# untitled.net
KiCad netlist of a schematic drawn in EAGLE
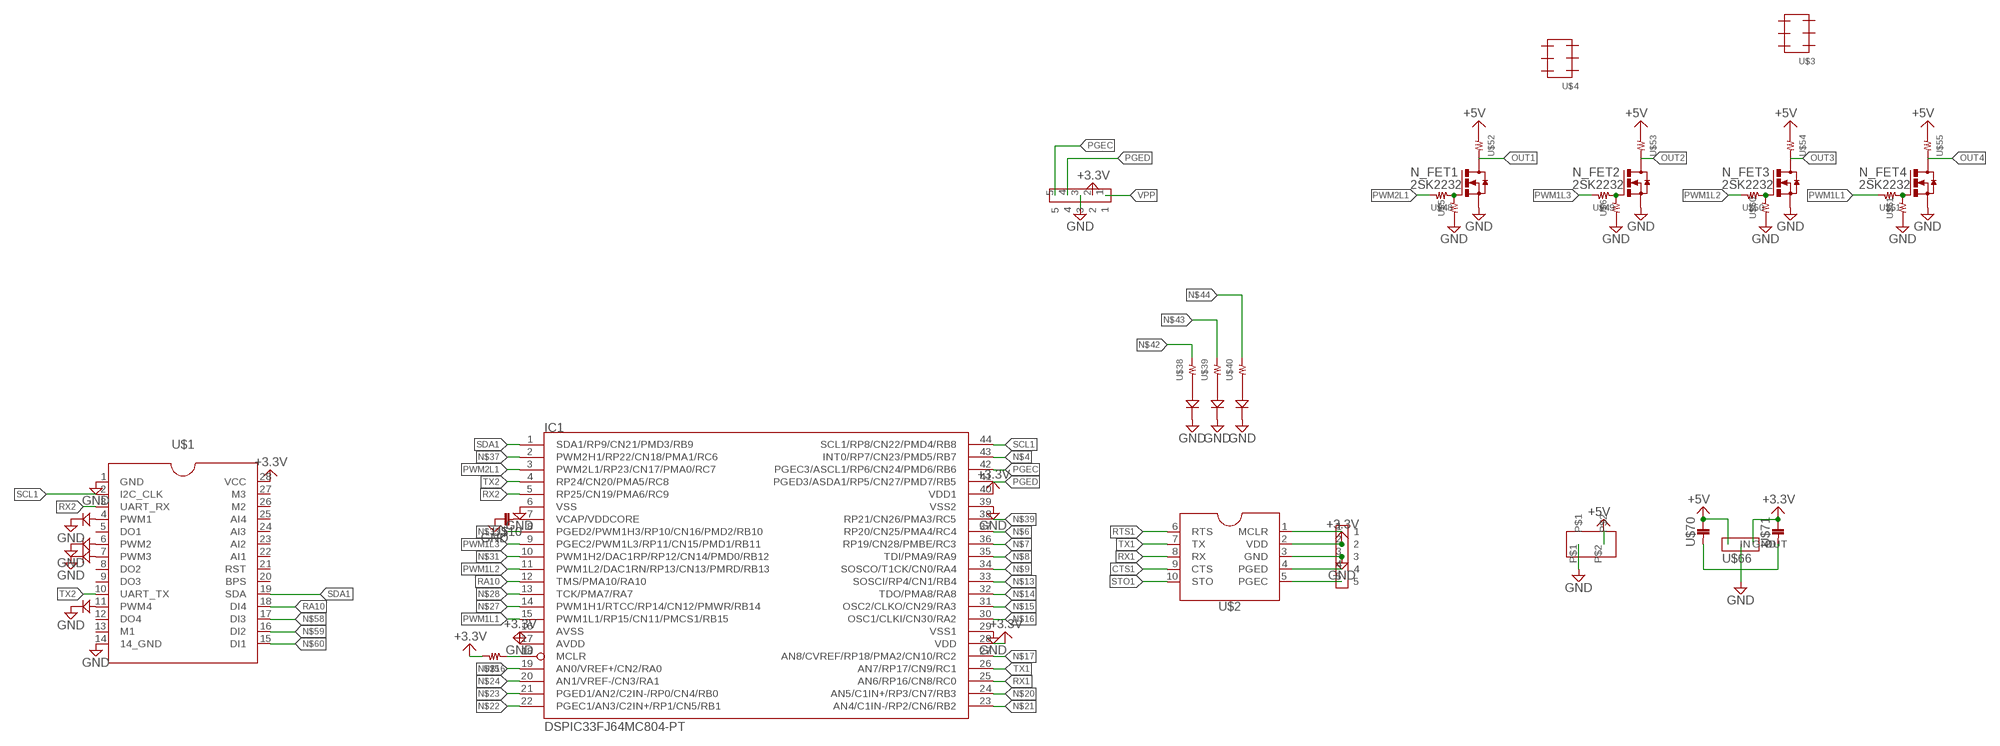
[diagram p0: schematic, sheet 1]

(export (version "E")
  (design (tool "Eeschema 10.0.6"))
  (components
    (comp (ref "IC1")
      (value "DSPIC33FJ64MC804-PT")
      (footprint "eagle-import:TQFP44")
      (libsource (lib "eagle-import") (part "DSPIC33FJ64MC804-PT"))
    )
    (comp (ref "N_FET1")
      (value "2SK2232")
      (footprint "eagle-import:TO-220_V")
      (libsource (lib "eagle-import") (part "2SK2232"))
    )
    (comp (ref "N_FET2")
      (value "2SK2232")
      (footprint "eagle-import:TO-220_V")
      (libsource (lib "eagle-import") (part "2SK2232"))
    )
    (comp (ref "N_FET3")
      (value "2SK2232")
      (footprint "eagle-import:TO-220_V")
      (libsource (lib "eagle-import") (part "2SK2232"))
    )
    (comp (ref "N_FET4")
      (value "2SK2232")
      (footprint "eagle-import:TO-220_V")
      (libsource (lib "eagle-import") (part "2SK2232"))
    )
    (comp (ref "U$1")
      (value "TWE-LITE")
      (footprint "eagle-import:DIP28")
      (libsource (lib "eagle-import") (part "TWE-LITE"))
    )
    (comp (ref "U$2")
      (value "SBDBT")
      (footprint "eagle-import:DIL10")
      (libsource (lib "eagle-import") (part "SBDBT"))
    )
    (comp (ref "U$3")
      (value "PIN_HEADER_32")
      (footprint "eagle-import:PIN_HEADER_3_2")
      (libsource (lib "eagle-import") (part "PIN_HEADER_32"))
    )
    (comp (ref "U$4")
      (value "PIN_HEADER_32")
      (footprint "eagle-import:PIN_HEADER_3_2")
      (libsource (lib "eagle-import") (part "PIN_HEADER_32"))
    )
    (comp (ref "U$5")
      (value "RESISTOR__SMD")
      (footprint "eagle-import:1608")
      (libsource (lib "eagle-import") (part "RESISTOR__SMD"))
    )
    (comp (ref "U$6")
      (value "RESISTOR__SMD")
      (footprint "eagle-import:1608")
      (libsource (lib "eagle-import") (part "RESISTOR__SMD"))
    )
    (comp (ref "U$10")
      (value "2012")
      (footprint "eagle-import:2012")
      (libsource (lib "eagle-import") (part "2012"))
    )
    (comp (ref "U$16")
      (value "RESISTOR__SMD")
      (footprint "eagle-import:1608")
      (libsource (lib "eagle-import") (part "RESISTOR__SMD"))
    )
    (comp (ref "U$18")
      (value "PIN_HEADER_5")
      (footprint "eagle-import:PIN_HEADER_5")
      (libsource (lib "eagle-import") (part "PIN_HEADER_5"))
    )
    (comp (ref "U$24")
      (value "PIN_HEADER_5")
      (footprint "eagle-import:PIN_HEADER_5")
      (libsource (lib "eagle-import") (part "PIN_HEADER_5"))
    )
    (comp (ref "U$27")
      (value "5MMLED")
      (footprint "eagle-import:5MM")
      (libsource (lib "eagle-import") (part "5MMLED"))
    )
    (comp (ref "U$28")
      (value "5MMLED")
      (footprint "eagle-import:5MM")
      (libsource (lib "eagle-import") (part "5MMLED"))
    )
    (comp (ref "U$29")
      (value "5MMLED")
      (footprint "eagle-import:5MM")
      (libsource (lib "eagle-import") (part "5MMLED"))
    )
    (comp (ref "U$30")
      (value "5MMLED")
      (footprint "eagle-import:5MM")
      (libsource (lib "eagle-import") (part "5MMLED"))
    )
    (comp (ref "U$35")
      (value "3MMLED")
      (footprint "eagle-import:3MM")
      (libsource (lib "eagle-import") (part "3MMLED"))
    )
    (comp (ref "U$36")
      (value "3MMLED")
      (footprint "eagle-import:3MM")
      (libsource (lib "eagle-import") (part "3MMLED"))
    )
    (comp (ref "U$37")
      (value "3MMLED")
      (footprint "eagle-import:3MM")
      (libsource (lib "eagle-import") (part "3MMLED"))
    )
    (comp (ref "U$38")
      (value "RESISTOR__SMD")
      (footprint "eagle-import:1608")
      (libsource (lib "eagle-import") (part "RESISTOR__SMD"))
    )
    (comp (ref "U$39")
      (value "RESISTOR__SMD")
      (footprint "eagle-import:1608")
      (libsource (lib "eagle-import") (part "RESISTOR__SMD"))
    )
    (comp (ref "U$40")
      (value "RESISTOR__SMD")
      (footprint "eagle-import:1608")
      (libsource (lib "eagle-import") (part "RESISTOR__SMD"))
    )
    (comp (ref "U$48")
      (value "RESISTOR__SMD")
      (footprint "eagle-import:1608")
      (libsource (lib "eagle-import") (part "RESISTOR__SMD"))
    )
    (comp (ref "U$49")
      (value "RESISTOR__SMD")
      (footprint "eagle-import:1608")
      (libsource (lib "eagle-import") (part "RESISTOR__SMD"))
    )
    (comp (ref "U$50")
      (value "RESISTOR__SMD")
      (footprint "eagle-import:1608")
      (libsource (lib "eagle-import") (part "RESISTOR__SMD"))
    )
    (comp (ref "U$51")
      (value "RESISTOR__SMD")
      (footprint "eagle-import:1608")
      (libsource (lib "eagle-import") (part "RESISTOR__SMD"))
    )
    (comp (ref "U$52")
      (value "RESISTOR__SMD")
      (footprint "eagle-import:1608")
      (libsource (lib "eagle-import") (part "RESISTOR__SMD"))
    )
    (comp (ref "U$53")
      (value "RESISTOR__SMD")
      (footprint "eagle-import:1608")
      (libsource (lib "eagle-import") (part "RESISTOR__SMD"))
    )
    (comp (ref "U$54")
      (value "RESISTOR__SMD")
      (footprint "eagle-import:1608")
      (libsource (lib "eagle-import") (part "RESISTOR__SMD"))
    )
    (comp (ref "U$55")
      (value "RESISTOR__SMD")
      (footprint "eagle-import:1608")
      (libsource (lib "eagle-import") (part "RESISTOR__SMD"))
    )
    (comp (ref "U$60")
      (value "RESISTOR__SMD")
      (footprint "eagle-import:1608")
      (libsource (lib "eagle-import") (part "RESISTOR__SMD"))
    )
    (comp (ref "U$61")
      (value "RESISTOR__SMD")
      (footprint "eagle-import:1608")
      (libsource (lib "eagle-import") (part "RESISTOR__SMD"))
    )
    (comp (ref "U$66")
      (value "TA48M033F")
      (footprint "eagle-import:ＴＡ４８")
      (libsource (lib "eagle-import") (part "TA48M033F"))
    )
    (comp (ref "U$70")
      (value "1608")
      (footprint "eagle-import:1608")
      (libsource (lib "eagle-import") (part "1608"))
    )
    (comp (ref "U$71")
      (value "3225")
      (footprint "eagle-import:3225")
      (libsource (lib "eagle-import") (part "3225"))
    )
    (comp (ref "U$72")
      (value "PIN_HEADER_2")
      (footprint "eagle-import:PIN_HEADER_2S")
      (libsource (lib "eagle-import") (part "PIN_HEADER_2"))
    )
  )
  (nets
    (net (code "1") (name "+3.3V") (class "Default")
      (node (ref "IC1") (pin "17") (pinfunction "AVDD_17") (pintype "power_in"))
      (node (ref "IC1") (pin "28") (pinfunction "VDD_28") (pintype "power_in"))
      (node (ref "IC1") (pin "40") (pinfunction "VDD1_40") (pintype "power_in"))
      (node (ref "U$1") (pin "28") (pinfunction "VCC_28") (pintype "passive"))
      (node (ref "U$16") (pin "2") (pinfunction "P$2_2") (pintype "passive"))
      (node (ref "U$18") (pin "2") (pinfunction "2_2") (pintype "bidirectional"))
      (node (ref "U$2") (pin "2") (pinfunction "VDD_2") (pintype "passive"))
      (node (ref "U$24") (pin "2") (pinfunction "2_2") (pintype "bidirectional"))
      (node (ref "U$66") (pin "3") (pinfunction "OUT_3") (pintype "bidirectional"))
      (node (ref "U$71") (pin "P$1") (pinfunction "1_P$1") (pintype "passive"))
    )
    (net (code "2") (name "+5V") (class "Default")
      (node (ref "U$52") (pin "1") (pinfunction "P$1_1") (pintype "passive"))
      (node (ref "U$53") (pin "1") (pinfunction "P$1_1") (pintype "passive"))
      (node (ref "U$54") (pin "1") (pinfunction "P$1_1") (pintype "passive"))
      (node (ref "U$55") (pin "1") (pinfunction "P$1_1") (pintype "passive"))
      (node (ref "U$66") (pin "1") (pinfunction "IN_1") (pintype "bidirectional"))
      (node (ref "U$70") (pin "P$1") (pinfunction "1_P$1") (pintype "passive"))
      (node (ref "U$72") (pin "P$2") (pinfunction "P$2_P$2") (pintype "bidirectional"))
    )
    (net (code "3") (name "CTS1") (class "Default")
      (node (ref "U$2") (pin "9") (pinfunction "CTS_9") (pintype "passive"))
    )
    (net (code "4") (name "GND") (class "Default")
      (node (ref "IC1") (pin "16") (pinfunction "AVSS_16") (pintype "power_in"))
      (node (ref "IC1") (pin "29") (pinfunction "VSS1_29") (pintype "power_in"))
      (node (ref "IC1") (pin "39") (pinfunction "VSS2_39") (pintype "power_in"))
      (node (ref "IC1") (pin "6") (pinfunction "VSS_6") (pintype "power_in"))
      (node (ref "N_FET1") (pin "3") (pinfunction "S_3") (pintype "passive"))
      (node (ref "N_FET2") (pin "3") (pinfunction "S_3") (pintype "passive"))
      (node (ref "N_FET3") (pin "3") (pinfunction "S_3") (pintype "passive"))
      (node (ref "N_FET4") (pin "3") (pinfunction "S_3") (pintype "passive"))
      (node (ref "U$1") (pin "1") (pinfunction "GND_1") (pintype "passive"))
      (node (ref "U$1") (pin "14") (pinfunction "14_GND_14") (pintype "passive"))
      (node (ref "U$10") (pin "1") (pinfunction "1_1") (pintype "passive"))
      (node (ref "U$18") (pin "3") (pinfunction "3_3") (pintype "bidirectional"))
      (node (ref "U$2") (pin "3") (pinfunction "GND_3") (pintype "passive"))
      (node (ref "U$24") (pin "3") (pinfunction "3_3") (pintype "bidirectional"))
      (node (ref "U$27") (pin "K") (pinfunction "K_K") (pintype "bidirectional"))
      (node (ref "U$28") (pin "K") (pinfunction "K_K") (pintype "bidirectional"))
      (node (ref "U$29") (pin "K") (pinfunction "K_K") (pintype "bidirectional"))
      (node (ref "U$30") (pin "K") (pinfunction "K_K") (pintype "bidirectional"))
      (node (ref "U$35") (pin "K") (pinfunction "K_K") (pintype "bidirectional"))
      (node (ref "U$36") (pin "K") (pinfunction "K_K") (pintype "bidirectional"))
      (node (ref "U$37") (pin "K") (pinfunction "K_K") (pintype "bidirectional"))
      (node (ref "U$5") (pin "1") (pinfunction "P$1_1") (pintype "passive"))
      (node (ref "U$6") (pin "1") (pinfunction "P$1_1") (pintype "passive"))
      (node (ref "U$60") (pin "1") (pinfunction "P$1_1") (pintype "passive"))
      (node (ref "U$61") (pin "1") (pinfunction "P$1_1") (pintype "passive"))
      (node (ref "U$66") (pin "2") (pinfunction "GND_2") (pintype "bidirectional"))
      (node (ref "U$70") (pin "P$2") (pinfunction "2_P$2") (pintype "passive"))
      (node (ref "U$71") (pin "P$2") (pinfunction "2_P$2") (pintype "passive"))
      (node (ref "U$72") (pin "P$1") (pinfunction "P$1_P$1") (pintype "bidirectional"))
    )
    (net (code "5") (name "N$4") (class "Default")
      (node (ref "IC1") (pin "43") (pinfunction "INT0/RP7/CN23/PMD5/RB7_43") (pintype "bidirectional"))
    )
    (net (code "6") (name "N$6") (class "Default")
      (node (ref "IC1") (pin "37") (pinfunction "RP20/CN25/PMA4/RC4_37") (pintype "bidirectional"))
    )
    (net (code "7") (name "N$7") (class "Default")
      (node (ref "IC1") (pin "36") (pinfunction "RP19/CN28/PMBE/RC3_36") (pintype "bidirectional"))
    )
    (net (code "8") (name "N$8") (class "Default")
      (node (ref "IC1") (pin "35") (pinfunction "TDI/PMA9/RA9_35") (pintype "bidirectional"))
    )
    (net (code "9") (name "N$9") (class "Default")
      (node (ref "IC1") (pin "34") (pinfunction "SOSCO/T1CK/CN0/RA4_34") (pintype "bidirectional"))
    )
    (net (code "10") (name "N$13") (class "Default")
      (node (ref "IC1") (pin "33") (pinfunction "SOSCI/RP4/CN1/RB4_33") (pintype "bidirectional"))
    )
    (net (code "11") (name "N$14") (class "Default")
      (node (ref "IC1") (pin "32") (pinfunction "TDO/PMA8/RA8_32") (pintype "bidirectional"))
    )
    (net (code "12") (name "N$15") (class "Default")
      (node (ref "IC1") (pin "31") (pinfunction "OSC2/CLKO/CN29/RA3_31") (pintype "bidirectional"))
    )
    (net (code "13") (name "N$16") (class "Default")
      (node (ref "IC1") (pin "30") (pinfunction "OSC1/CLKI/CN30/RA2_30") (pintype "bidirectional"))
    )
    (net (code "14") (name "N$17") (class "Default")
      (node (ref "IC1") (pin "27") (pinfunction "AN8/CVREF/RP18/PMA2/CN10/RC2_27") (pintype "bidirectional"))
    )
    (net (code "15") (name "N$20") (class "Default")
      (node (ref "IC1") (pin "24") (pinfunction "AN5/C1IN+/RP3/CN7/RB3_24") (pintype "bidirectional"))
    )
    (net (code "16") (name "N$21") (class "Default")
      (node (ref "IC1") (pin "23") (pinfunction "AN4/C1IN-/RP2/CN6/RB2_23") (pintype "bidirectional"))
    )
    (net (code "17") (name "N$22") (class "Default")
      (node (ref "IC1") (pin "22") (pinfunction "PGEC1/AN3/C2IN+/RP1/CN5/RB1_22") (pintype "bidirectional"))
    )
    (net (code "18") (name "N$23") (class "Default")
      (node (ref "IC1") (pin "21") (pinfunction "PGED1/AN2/C2IN-/RP0/CN4/RB0_21") (pintype "bidirectional"))
    )
    (net (code "19") (name "N$24") (class "Default")
      (node (ref "IC1") (pin "20") (pinfunction "AN1/VREF-/CN3/RA1_20") (pintype "bidirectional"))
    )
    (net (code "20") (name "N$25") (class "Default")
      (node (ref "IC1") (pin "19") (pinfunction "AN0/VREF+/CN2/RA0_19") (pintype "bidirectional"))
    )
    (net (code "21") (name "N$27") (class "Default")
      (node (ref "IC1") (pin "14") (pinfunction "PWM1H1/RTCC/RP14/CN12/PMWR/RB14_14") (pintype "bidirectional"))
    )
    (net (code "22") (name "N$28") (class "Default")
      (node (ref "IC1") (pin "13") (pinfunction "TCK/PMA7/RA7_13") (pintype "bidirectional"))
    )
    (net (code "23") (name "N$31") (class "Default")
      (node (ref "IC1") (pin "10") (pinfunction "PWM1H2/DAC1RP/RP12/CN14/PMD0/RB12_10") (pintype "bidirectional"))
    )
    (net (code "24") (name "N$33") (class "Default")
      (node (ref "IC1") (pin "8") (pinfunction "PGED2/PWM1H3/RP10/CN16/PMD2/RB10_8") (pintype "bidirectional"))
    )
    (net (code "25") (name "N$37") (class "Default")
      (node (ref "IC1") (pin "2") (pinfunction "PWM2H1/RP22/CN18/PMA1/RC6_2") (pintype "bidirectional"))
    )
    (net (code "26") (name "N$39") (class "Default")
      (node (ref "IC1") (pin "38") (pinfunction "RP21/CN26/PMA3/RC5_38") (pintype "bidirectional"))
    )
    (net (code "27") (name "N$42") (class "Default")
      (node (ref "U$38") (pin "2") (pinfunction "P$2_2") (pintype "passive"))
    )
    (net (code "28") (name "N$43") (class "Default")
      (node (ref "U$39") (pin "2") (pinfunction "P$2_2") (pintype "passive"))
    )
    (net (code "29") (name "N$44") (class "Default")
      (node (ref "U$40") (pin "2") (pinfunction "P$2_2") (pintype "passive"))
    )
    (net (code "30") (name "N$58") (class "Default")
      (node (ref "U$1") (pin "17") (pinfunction "DI3_17") (pintype "passive"))
    )
    (net (code "31") (name "N$59") (class "Default")
      (node (ref "U$1") (pin "16") (pinfunction "DI2_16") (pintype "passive"))
    )
    (net (code "32") (name "N$60") (class "Default")
      (node (ref "U$1") (pin "15") (pinfunction "DI1_15") (pintype "passive"))
    )
    (net (code "33") (name "Net-(IC1-VCAP{slash}VDDCORE)") (class "Default")
      (node (ref "IC1") (pin "7") (pinfunction "VCAP/VDDCORE_7") (pintype "power_in"))
      (node (ref "U$10") (pin "2") (pinfunction "2_2") (pintype "passive"))
    )
    (net (code "34") (name "Net-(N_FET1-G)") (class "Default")
      (node (ref "N_FET1") (pin "1") (pinfunction "G_1") (pintype "passive"))
      (node (ref "U$48") (pin "1") (pinfunction "P$1_1") (pintype "passive"))
      (node (ref "U$5") (pin "2") (pinfunction "P$2_2") (pintype "passive"))
    )
    (net (code "35") (name "Net-(N_FET2-G)") (class "Default")
      (node (ref "N_FET2") (pin "1") (pinfunction "G_1") (pintype "passive"))
      (node (ref "U$49") (pin "1") (pinfunction "P$1_1") (pintype "passive"))
      (node (ref "U$6") (pin "2") (pinfunction "P$2_2") (pintype "passive"))
    )
    (net (code "36") (name "Net-(N_FET3-G)") (class "Default")
      (node (ref "N_FET3") (pin "1") (pinfunction "G_1") (pintype "passive"))
      (node (ref "U$50") (pin "1") (pinfunction "P$1_1") (pintype "passive"))
      (node (ref "U$60") (pin "2") (pinfunction "P$2_2") (pintype "passive"))
    )
    (net (code "37") (name "Net-(N_FET4-G)") (class "Default")
      (node (ref "N_FET4") (pin "1") (pinfunction "G_1") (pintype "passive"))
      (node (ref "U$51") (pin "1") (pinfunction "P$1_1") (pintype "passive"))
      (node (ref "U$61") (pin "2") (pinfunction "P$2_2") (pintype "passive"))
    )
    (net (code "38") (name "Net-(U$1-PWM1)") (class "Default")
      (node (ref "U$1") (pin "4") (pinfunction "PWM1_4") (pintype "passive"))
      (node (ref "U$27") (pin "A") (pinfunction "A_A") (pintype "bidirectional"))
    )
    (net (code "39") (name "Net-(U$1-PWM2)") (class "Default")
      (node (ref "U$1") (pin "6") (pinfunction "PWM2_6") (pintype "passive"))
      (node (ref "U$28") (pin "A") (pinfunction "A_A") (pintype "bidirectional"))
    )
    (net (code "40") (name "Net-(U$1-PWM3)") (class "Default")
      (node (ref "U$1") (pin "7") (pinfunction "PWM3_7") (pintype "passive"))
      (node (ref "U$29") (pin "A") (pinfunction "A_A") (pintype "bidirectional"))
    )
    (net (code "41") (name "Net-(U$1-PWM4)") (class "Default")
      (node (ref "U$1") (pin "11") (pinfunction "PWM4_11") (pintype "passive"))
      (node (ref "U$30") (pin "A") (pinfunction "A_A") (pintype "bidirectional"))
    )
    (net (code "42") (name "Net-(U$2-MCLR)") (class "Default")
      (node (ref "U$2") (pin "1") (pinfunction "MCLR_1") (pintype "passive"))
      (node (ref "U$24") (pin "1") (pinfunction "1_1") (pintype "bidirectional"))
    )
    (net (code "43") (name "Net-(U$2-PGEC)") (class "Default")
      (node (ref "U$2") (pin "5") (pinfunction "PGEC_5") (pintype "passive"))
      (node (ref "U$24") (pin "5") (pinfunction "5_5") (pintype "bidirectional"))
    )
    (net (code "44") (name "Net-(U$2-PGED)") (class "Default")
      (node (ref "U$2") (pin "4") (pinfunction "PGED_4") (pintype "passive"))
      (node (ref "U$24") (pin "4") (pinfunction "4_4") (pintype "bidirectional"))
    )
    (net (code "45") (name "Net-(U$38-P$1)") (class "Default")
      (node (ref "U$35") (pin "A") (pinfunction "A_A") (pintype "bidirectional"))
      (node (ref "U$38") (pin "1") (pinfunction "P$1_1") (pintype "passive"))
    )
    (net (code "46") (name "Net-(U$39-P$1)") (class "Default")
      (node (ref "U$36") (pin "A") (pinfunction "A_A") (pintype "bidirectional"))
      (node (ref "U$39") (pin "1") (pinfunction "P$1_1") (pintype "passive"))
    )
    (net (code "47") (name "Net-(U$40-P$1)") (class "Default")
      (node (ref "U$37") (pin "A") (pinfunction "A_A") (pintype "bidirectional"))
      (node (ref "U$40") (pin "1") (pinfunction "P$1_1") (pintype "passive"))
    )
    (net (code "48") (name "OUT1") (class "Default")
      (node (ref "N_FET1") (pin "2") (pinfunction "D_2") (pintype "passive"))
      (node (ref "U$52") (pin "2") (pinfunction "P$2_2") (pintype "passive"))
    )
    (net (code "49") (name "OUT2") (class "Default")
      (node (ref "N_FET2") (pin "2") (pinfunction "D_2") (pintype "passive"))
      (node (ref "U$53") (pin "2") (pinfunction "P$2_2") (pintype "passive"))
    )
    (net (code "50") (name "OUT3") (class "Default")
      (node (ref "N_FET3") (pin "2") (pinfunction "D_2") (pintype "passive"))
      (node (ref "U$54") (pin "2") (pinfunction "P$2_2") (pintype "passive"))
    )
    (net (code "51") (name "OUT4") (class "Default")
      (node (ref "N_FET4") (pin "2") (pinfunction "D_2") (pintype "passive"))
      (node (ref "U$55") (pin "2") (pinfunction "P$2_2") (pintype "passive"))
    )
    (net (code "52") (name "PGEC") (class "Default")
      (node (ref "IC1") (pin "42") (pinfunction "PGEC3/ASCL1/RP6/CN24/PMD6/RB6_42") (pintype "bidirectional"))
      (node (ref "U$18") (pin "5") (pinfunction "5_5") (pintype "bidirectional"))
    )
    (net (code "53") (name "PGED") (class "Default")
      (node (ref "IC1") (pin "41") (pinfunction "PGED3/ASDA1/RP5/CN27/PMD7/RB5_41") (pintype "bidirectional"))
      (node (ref "U$18") (pin "4") (pinfunction "4_4") (pintype "bidirectional"))
    )
    (net (code "54") (name "PWM1L1") (class "Default")
      (node (ref "IC1") (pin "15") (pinfunction "PWM1L1/RP15/CN11/PMCS1/RB15_15") (pintype "bidirectional"))
      (node (ref "U$51") (pin "2") (pinfunction "P$2_2") (pintype "passive"))
    )
    (net (code "55") (name "PWM1L2") (class "Default")
      (node (ref "IC1") (pin "11") (pinfunction "PWM1L2/DAC1RN/RP13/CN13/PMRD/RB13_11") (pintype "bidirectional"))
      (node (ref "U$50") (pin "2") (pinfunction "P$2_2") (pintype "passive"))
    )
    (net (code "56") (name "PWM1L3") (class "Default")
      (node (ref "IC1") (pin "9") (pinfunction "PGEC2/PWM1L3/RP11/CN15/PMD1/RB11_9") (pintype "bidirectional"))
      (node (ref "U$49") (pin "2") (pinfunction "P$2_2") (pintype "passive"))
    )
    (net (code "57") (name "PWM2L1") (class "Default")
      (node (ref "IC1") (pin "3") (pinfunction "PWM2L1/RP23/CN17/PMA0/RC7_3") (pintype "bidirectional"))
      (node (ref "U$48") (pin "2") (pinfunction "P$2_2") (pintype "passive"))
    )
    (net (code "58") (name "RA10") (class "Default")
      (node (ref "IC1") (pin "12") (pinfunction "TMS/PMA10/RA10_12") (pintype "bidirectional"))
      (node (ref "U$1") (pin "18") (pinfunction "DI4_18") (pintype "passive"))
    )
    (net (code "59") (name "RTS1") (class "Default")
      (node (ref "U$2") (pin "6") (pinfunction "RTS_6") (pintype "passive"))
    )
    (net (code "60") (name "RX1") (class "Default")
      (node (ref "IC1") (pin "25") (pinfunction "AN6/RP16/CN8/RC0_25") (pintype "bidirectional"))
      (node (ref "U$2") (pin "8") (pinfunction "RX_8") (pintype "passive"))
    )
    (net (code "61") (name "RX2") (class "Default")
      (node (ref "IC1") (pin "5") (pinfunction "RP25/CN19/PMA6/RC9_5") (pintype "bidirectional"))
      (node (ref "U$1") (pin "3") (pinfunction "UART_RX_3") (pintype "passive"))
    )
    (net (code "62") (name "SCL1") (class "Default")
      (node (ref "IC1") (pin "44") (pinfunction "SCL1/RP8/CN22/PMD4/RB8_44") (pintype "bidirectional"))
      (node (ref "U$1") (pin "2") (pinfunction "I2C_CLK_2") (pintype "passive"))
    )
    (net (code "63") (name "SDA1") (class "Default")
      (node (ref "IC1") (pin "1") (pinfunction "SDA1/RP9/CN21/PMD3/RB9_1") (pintype "bidirectional"))
      (node (ref "U$1") (pin "19") (pinfunction "SDA_19") (pintype "passive"))
    )
    (net (code "64") (name "STO1") (class "Default")
      (node (ref "U$2") (pin "10") (pinfunction "STO_10") (pintype "passive"))
    )
    (net (code "65") (name "TX1") (class "Default")
      (node (ref "IC1") (pin "26") (pinfunction "AN7/RP17/CN9/RC1_26") (pintype "bidirectional"))
      (node (ref "U$2") (pin "7") (pinfunction "TX_7") (pintype "passive"))
    )
    (net (code "66") (name "TX2") (class "Default")
      (node (ref "IC1") (pin "4") (pinfunction "RP24/CN20/PMA5/RC8_4") (pintype "bidirectional"))
      (node (ref "U$1") (pin "10") (pinfunction "UART_TX_10") (pintype "passive"))
    )
    (net (code "67") (name "VPP") (class "Default")
      (node (ref "IC1") (pin "18") (pinfunction "MCLR_18") (pintype "input"))
      (node (ref "U$16") (pin "1") (pinfunction "P$1_1") (pintype "passive"))
      (node (ref "U$18") (pin "1") (pinfunction "1_1") (pintype "bidirectional"))
    )
    (net (code "68") (name "unconnected-(U$1-AI1-Pad22)") (class "Default")
      (node (ref "U$1") (pin "22") (pinfunction "AI1_22") (pintype "passive"))
    )
    (net (code "69") (name "unconnected-(U$1-AI2-Pad23)") (class "Default")
      (node (ref "U$1") (pin "23") (pinfunction "AI2_23") (pintype "passive"))
    )
    (net (code "70") (name "unconnected-(U$1-AI3-Pad24)") (class "Default")
      (node (ref "U$1") (pin "24") (pinfunction "AI3_24") (pintype "passive"))
    )
    (net (code "71") (name "unconnected-(U$1-AI4-Pad25)") (class "Default")
      (node (ref "U$1") (pin "25") (pinfunction "AI4_25") (pintype "passive"))
    )
    (net (code "72") (name "unconnected-(U$1-BPS-Pad20)") (class "Default")
      (node (ref "U$1") (pin "20") (pinfunction "BPS_20") (pintype "passive"))
    )
    (net (code "73") (name "unconnected-(U$1-DO1-Pad5)") (class "Default")
      (node (ref "U$1") (pin "5") (pinfunction "DO1_5") (pintype "passive"))
    )
    (net (code "74") (name "unconnected-(U$1-DO2-Pad8)") (class "Default")
      (node (ref "U$1") (pin "8") (pinfunction "DO2_8") (pintype "passive"))
    )
    (net (code "75") (name "unconnected-(U$1-DO3-Pad9)") (class "Default")
      (node (ref "U$1") (pin "9") (pinfunction "DO3_9") (pintype "passive"))
    )
    (net (code "76") (name "unconnected-(U$1-DO4-Pad12)") (class "Default")
      (node (ref "U$1") (pin "12") (pinfunction "DO4_12") (pintype "passive"))
    )
    (net (code "77") (name "unconnected-(U$1-M1-Pad13)") (class "Default")
      (node (ref "U$1") (pin "13") (pinfunction "M1_13") (pintype "passive"))
    )
    (net (code "78") (name "unconnected-(U$1-M2-Pad26)") (class "Default")
      (node (ref "U$1") (pin "26") (pinfunction "M2_26") (pintype "passive"))
    )
    (net (code "79") (name "unconnected-(U$1-M3-Pad27)") (class "Default")
      (node (ref "U$1") (pin "27") (pinfunction "M3_27") (pintype "passive"))
    )
    (net (code "80") (name "unconnected-(U$1-RST-Pad21)") (class "Default")
      (node (ref "U$1") (pin "21") (pinfunction "RST_21") (pintype "passive"))
    )
    (net (code "81") (name "unconnected-(U$3-1-PadP$1)") (class "Default")
      (node (ref "U$3") (pin "P$1") (pinfunction "1_P$1") (pintype "bidirectional"))
    )
    (net (code "82") (name "unconnected-(U$3-2-PadP$2)") (class "Default")
      (node (ref "U$3") (pin "P$2") (pinfunction "2_P$2") (pintype "bidirectional"))
    )
    (net (code "83") (name "unconnected-(U$3-3-PadP$3)") (class "Default")
      (node (ref "U$3") (pin "P$3") (pinfunction "3_P$3") (pintype "bidirectional"))
    )
    (net (code "84") (name "unconnected-(U$3-4-PadP$4)") (class "Default")
      (node (ref "U$3") (pin "P$4") (pinfunction "4_P$4") (pintype "bidirectional"))
    )
    (net (code "85") (name "unconnected-(U$3-5-PadP$5)") (class "Default")
      (node (ref "U$3") (pin "P$5") (pinfunction "5_P$5") (pintype "bidirectional"))
    )
    (net (code "86") (name "unconnected-(U$3-6-PadP$6)") (class "Default")
      (node (ref "U$3") (pin "P$6") (pinfunction "6_P$6") (pintype "bidirectional"))
    )
    (net (code "87") (name "unconnected-(U$4-1-PadP$1)") (class "Default")
      (node (ref "U$4") (pin "P$1") (pinfunction "1_P$1") (pintype "bidirectional"))
    )
    (net (code "88") (name "unconnected-(U$4-2-PadP$2)") (class "Default")
      (node (ref "U$4") (pin "P$2") (pinfunction "2_P$2") (pintype "bidirectional"))
    )
    (net (code "89") (name "unconnected-(U$4-3-PadP$3)") (class "Default")
      (node (ref "U$4") (pin "P$3") (pinfunction "3_P$3") (pintype "bidirectional"))
    )
    (net (code "90") (name "unconnected-(U$4-4-PadP$4)") (class "Default")
      (node (ref "U$4") (pin "P$4") (pinfunction "4_P$4") (pintype "bidirectional"))
    )
    (net (code "91") (name "unconnected-(U$4-5-PadP$5)") (class "Default")
      (node (ref "U$4") (pin "P$5") (pinfunction "5_P$5") (pintype "bidirectional"))
    )
    (net (code "92") (name "unconnected-(U$4-6-PadP$6)") (class "Default")
      (node (ref "U$4") (pin "P$6") (pinfunction "6_P$6") (pintype "bidirectional"))
    )
  )
)
